# Driver.net
KiCad netlist of a schematic drawn in Altium Designer
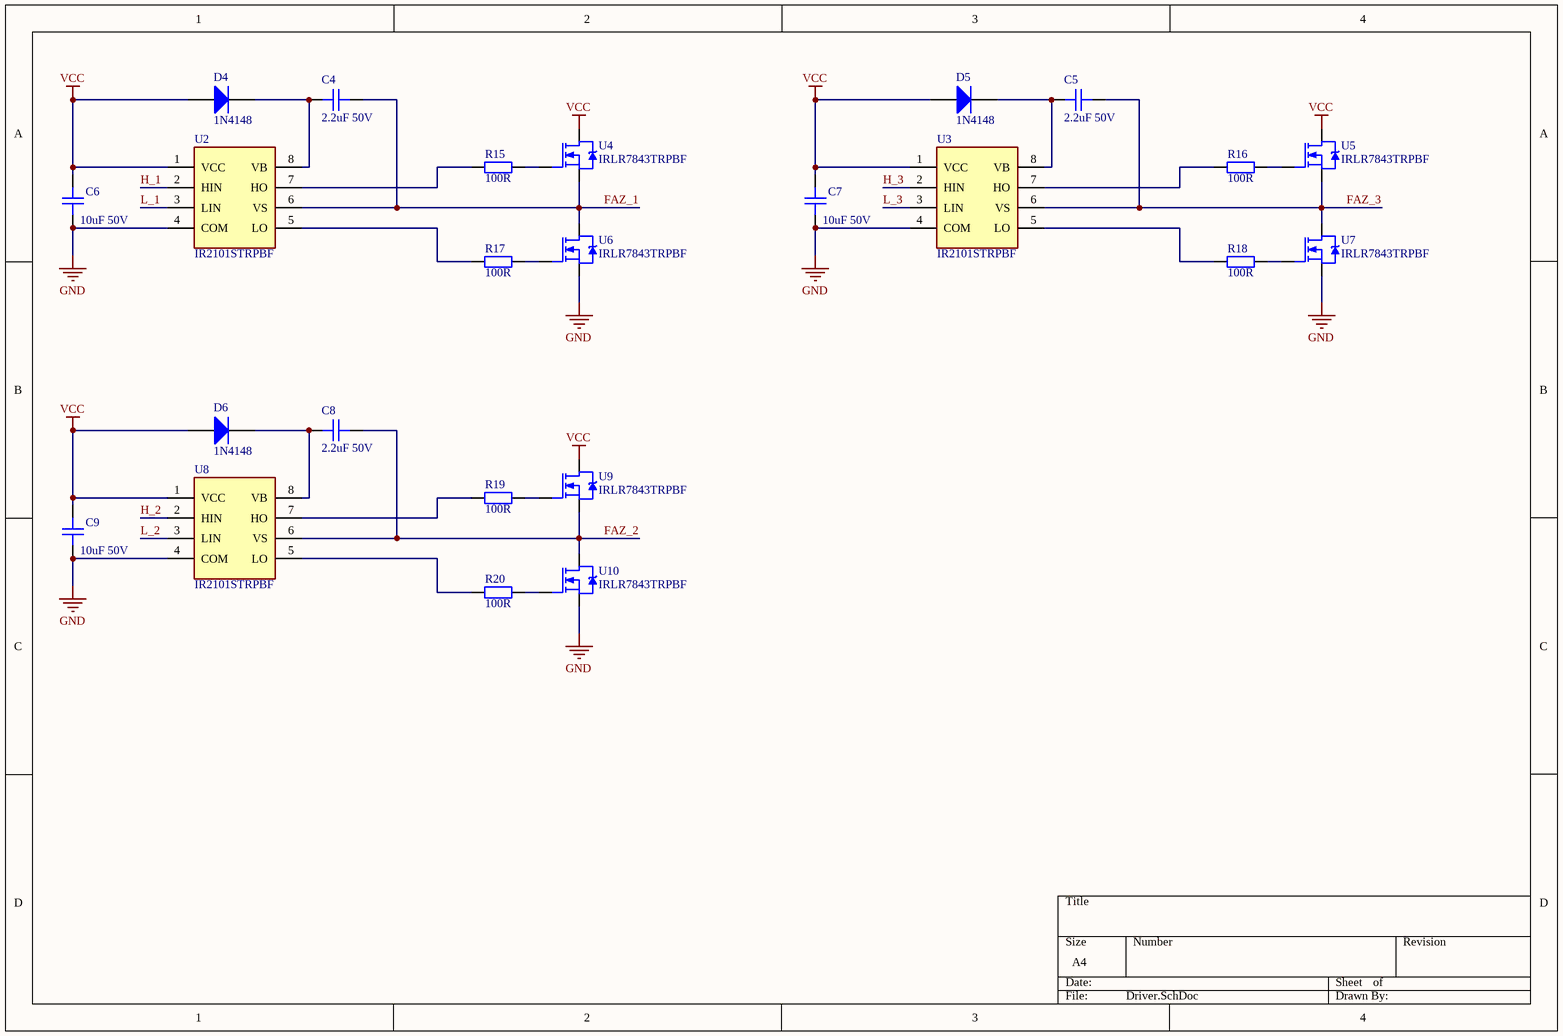
[diagram p0: Driver.SchDoc]

(export (version "E")
  (design (tool "Eeschema 10.0.6"))
  (components
    (comp (ref "C4")
      (value "CAP CER 2.2UF 50V X5R 1206")
      (footprint "CAP 1206/3216")
      (description "2.2µF ±10% 50V Ceramic Capacitor X5R 1206 (3216 Metric)")
      (fields (field (name "DEGER") "2.2uF 50V"))
      (libsource (lib "PROJE") (part "2.2uF 50V 1206"))
    )
    (comp (ref "C5")
      (value "CAP CER 2.2UF 50V X5R 1206")
      (footprint "CAP 1206/3216")
      (description "2.2µF ±10% 50V Ceramic Capacitor X5R 1206 (3216 Metric)")
      (fields (field (name "DEGER") "2.2uF 50V"))
      (libsource (lib "PROJE") (part "2.2uF 50V 1206"))
    )
    (comp (ref "C6")
      (value "CAP CER 10UF 50V X5R 1206")
      (footprint "CAP 1206/3216")
      (description "10µF ±10% 50V Ceramic Capacitor X5R 1206 (3216 Metric)")
      (fields (field (name "DEGER") "10uF 50V"))
      (libsource (lib "PROJE") (part "10uF 50V 1206"))
    )
    (comp (ref "C7")
      (value "CAP CER 10UF 50V X5R 1206")
      (footprint "CAP 1206/3216")
      (description "10µF ±10% 50V Ceramic Capacitor X5R 1206 (3216 Metric)")
      (fields (field (name "DEGER") "10uF 50V"))
      (libsource (lib "PROJE") (part "10uF 50V 1206"))
    )
    (comp (ref "C8")
      (value "CAP CER 2.2UF 50V X5R 1206")
      (footprint "CAP 1206/3216")
      (description "2.2µF ±10% 50V Ceramic Capacitor X5R 1206 (3216 Metric)")
      (fields (field (name "DEGER") "2.2uF 50V"))
      (libsource (lib "PROJE") (part "2.2uF 50V 1206"))
    )
    (comp (ref "C9")
      (value "CAP CER 10UF 50V X5R 1206")
      (footprint "CAP 1206/3216")
      (description "10µF ±10% 50V Ceramic Capacitor X5R 1206 (3216 Metric)")
      (fields (field (name "DEGER") "10uF 50V"))
      (libsource (lib "PROJE") (part "10uF 50V 1206"))
    )
    (comp (ref "D4")
      (value "1N4148 Diyot")
      (footprint "SOD-123")
      (description "DIODE GEN PURP 100V 150MA SOD123")
      (fields (field (name "DEGER") "1N4148"))
      (libsource (lib "PROJE") (part "1N4148"))
    )
    (comp (ref "D5")
      (value "1N4148 Diyot")
      (footprint "SOD-123")
      (description "DIODE GEN PURP 100V 150MA SOD123")
      (fields (field (name "DEGER") "1N4148"))
      (libsource (lib "PROJE") (part "1N4148"))
    )
    (comp (ref "D6")
      (value "1N4148 Diyot")
      (footprint "SOD-123")
      (description "DIODE GEN PURP 100V 150MA SOD123")
      (fields (field (name "DEGER") "1N4148"))
      (libsource (lib "PROJE") (part "1N4148"))
    )
    (comp (ref "R15")
      (value "RES SMD 100 OHM 1% 1/8W 0805")
      (footprint "RES_0805")
      (description "100 Ohms ±1% 0.125W, 1/8W Chip Resistor 0805 (2012 Metric) Moisture Resistant Thick Film")
      (fields (field (name "DEGER") "100R"))
      (libsource (lib "PROJE") (part "100R 0805"))
    )
    (comp (ref "R16")
      (value "RES SMD 100 OHM 1% 1/8W 0805")
      (footprint "RES_0805")
      (description "100 Ohms ±1% 0.125W, 1/8W Chip Resistor 0805 (2012 Metric) Moisture Resistant Thick Film")
      (fields (field (name "DEGER") "100R"))
      (libsource (lib "PROJE") (part "100R 0805"))
    )
    (comp (ref "R17")
      (value "RES SMD 100 OHM 1% 1/8W 0805")
      (footprint "RES_0805")
      (description "100 Ohms ±1% 0.125W, 1/8W Chip Resistor 0805 (2012 Metric) Moisture Resistant Thick Film")
      (fields (field (name "DEGER") "100R"))
      (libsource (lib "PROJE") (part "100R 0805"))
    )
    (comp (ref "R18")
      (value "RES SMD 100 OHM 1% 1/8W 0805")
      (footprint "RES_0805")
      (description "100 Ohms ±1% 0.125W, 1/8W Chip Resistor 0805 (2012 Metric) Moisture Resistant Thick Film")
      (fields (field (name "DEGER") "100R"))
      (libsource (lib "PROJE") (part "100R 0805"))
    )
    (comp (ref "R19")
      (value "RES SMD 100 OHM 1% 1/8W 0805")
      (footprint "RES_0805")
      (description "100 Ohms ±1% 0.125W, 1/8W Chip Resistor 0805 (2012 Metric) Moisture Resistant Thick Film")
      (fields (field (name "DEGER") "100R"))
      (libsource (lib "PROJE") (part "100R 0805"))
    )
    (comp (ref "R20")
      (value "RES SMD 100 OHM 1% 1/8W 0805")
      (footprint "RES_0805")
      (description "100 Ohms ±1% 0.125W, 1/8W Chip Resistor 0805 (2012 Metric) Moisture Resistant Thick Film")
      (fields (field (name "DEGER") "100R"))
      (libsource (lib "PROJE") (part "100R 0805"))
    )
    (comp (ref "U2")
      (value "IC GATE DRVR HALF-BRIDGE 8SOIC")
      (footprint "SOIC8")
      (description "Half-Bridge Gate Driver IC Non-Inverting 8-SOIC")
      (fields (field (name "DEGER") "IR2101STRPBF"))
      (libsource (lib "PROJE") (part "IR2101"))
    )
    (comp (ref "U3")
      (value "IC GATE DRVR HALF-BRIDGE 8SOIC")
      (footprint "SOIC8")
      (description "Half-Bridge Gate Driver IC Non-Inverting 8-SOIC")
      (fields (field (name "DEGER") "IR2101STRPBF"))
      (libsource (lib "PROJE") (part "IR2101"))
    )
    (comp (ref "U4")
      (value "MOSFET N-CH 30V 161A DPAK")
      (footprint "DPAK")
      (description "N-Channel 30V 161A (Tc) 140W (Tc) Surface Mount D-Pak")
      (fields (field (name "DEGER") "IRLR7843TRPBF"))
      (libsource (lib "PROJE") (part "IRLR7843"))
    )
    (comp (ref "U5")
      (value "MOSFET N-CH 30V 161A DPAK")
      (footprint "DPAK")
      (description "N-Channel 30V 161A (Tc) 140W (Tc) Surface Mount D-Pak")
      (fields (field (name "DEGER") "IRLR7843TRPBF"))
      (libsource (lib "PROJE") (part "IRLR7843"))
    )
    (comp (ref "U6")
      (value "MOSFET N-CH 30V 161A DPAK")
      (footprint "DPAK")
      (description "N-Channel 30V 161A (Tc) 140W (Tc) Surface Mount D-Pak")
      (fields (field (name "DEGER") "IRLR7843TRPBF"))
      (libsource (lib "PROJE") (part "IRLR7843"))
    )
    (comp (ref "U7")
      (value "MOSFET N-CH 30V 161A DPAK")
      (footprint "DPAK")
      (description "N-Channel 30V 161A (Tc) 140W (Tc) Surface Mount D-Pak")
      (fields (field (name "DEGER") "IRLR7843TRPBF"))
      (libsource (lib "PROJE") (part "IRLR7843"))
    )
    (comp (ref "U8")
      (value "IC GATE DRVR HALF-BRIDGE 8SOIC")
      (footprint "SOIC8")
      (description "Half-Bridge Gate Driver IC Non-Inverting 8-SOIC")
      (fields (field (name "DEGER") "IR2101STRPBF"))
      (libsource (lib "PROJE") (part "IR2101"))
    )
    (comp (ref "U9")
      (value "MOSFET N-CH 30V 161A DPAK")
      (footprint "DPAK")
      (description "N-Channel 30V 161A (Tc) 140W (Tc) Surface Mount D-Pak")
      (fields (field (name "DEGER") "IRLR7843TRPBF"))
      (libsource (lib "PROJE") (part "IRLR7843"))
    )
    (comp (ref "U10")
      (value "MOSFET N-CH 30V 161A DPAK")
      (footprint "DPAK")
      (description "N-Channel 30V 161A (Tc) 140W (Tc) Surface Mount D-Pak")
      (fields (field (name "DEGER") "IRLR7843TRPBF"))
      (libsource (lib "PROJE") (part "IRLR7843"))
    )
  )
  (nets
    (net (code "1") (name "/FAZ_1") (class "Default")
      (node (ref "C4") (pin "1") (pinfunction "1_1") (pintype "passive"))
      (node (ref "U2") (pin "6") (pinfunction "VS_6") (pintype "passive"))
      (node (ref "U4") (pin "3") (pinfunction "S_3") (pintype "passive"))
      (node (ref "U6") (pin "4") (pinfunction "D_4") (pintype "passive"))
    )
    (net (code "2") (name "/FAZ_2") (class "Default")
      (node (ref "C8") (pin "1") (pinfunction "1_1") (pintype "passive"))
      (node (ref "U10") (pin "4") (pinfunction "D_4") (pintype "passive"))
      (node (ref "U8") (pin "6") (pinfunction "VS_6") (pintype "passive"))
      (node (ref "U9") (pin "3") (pinfunction "S_3") (pintype "passive"))
    )
    (net (code "3") (name "/FAZ_3") (class "Default")
      (node (ref "C5") (pin "1") (pinfunction "1_1") (pintype "passive"))
      (node (ref "U3") (pin "6") (pinfunction "VS_6") (pintype "passive"))
      (node (ref "U5") (pin "3") (pinfunction "S_3") (pintype "passive"))
      (node (ref "U7") (pin "4") (pinfunction "D_4") (pintype "passive"))
    )
    (net (code "4") (name "/H_1") (class "Default")
      (node (ref "U2") (pin "2") (pinfunction "HIN_2") (pintype "passive"))
    )
    (net (code "5") (name "/H_2") (class "Default")
      (node (ref "U8") (pin "2") (pinfunction "HIN_2") (pintype "passive"))
    )
    (net (code "6") (name "/H_3") (class "Default")
      (node (ref "U3") (pin "2") (pinfunction "HIN_2") (pintype "passive"))
    )
    (net (code "7") (name "/L_1") (class "Default")
      (node (ref "U2") (pin "3") (pinfunction "LIN_3") (pintype "passive"))
    )
    (net (code "8") (name "/L_2") (class "Default")
      (node (ref "U8") (pin "3") (pinfunction "LIN_3") (pintype "passive"))
    )
    (net (code "9") (name "/L_3") (class "Default")
      (node (ref "U3") (pin "3") (pinfunction "LIN_3") (pintype "passive"))
    )
    (net (code "10") (name "GND") (class "Default")
      (node (ref "C6") (pin "1") (pinfunction "1_1") (pintype "passive"))
      (node (ref "C7") (pin "1") (pinfunction "1_1") (pintype "passive"))
      (node (ref "C9") (pin "1") (pinfunction "1_1") (pintype "passive"))
      (node (ref "U10") (pin "3") (pinfunction "S_3") (pintype "passive"))
      (node (ref "U2") (pin "4") (pinfunction "COM_4") (pintype "passive"))
      (node (ref "U3") (pin "4") (pinfunction "COM_4") (pintype "passive"))
      (node (ref "U6") (pin "3") (pinfunction "S_3") (pintype "passive"))
      (node (ref "U7") (pin "3") (pinfunction "S_3") (pintype "passive"))
      (node (ref "U8") (pin "4") (pinfunction "COM_4") (pintype "passive"))
    )
    (net (code "11") (name "Net-(D4-K)") (class "Default")
      (node (ref "C4") (pin "2") (pinfunction "2_2") (pintype "passive"))
      (node (ref "D4") (pin "2") (pinfunction "K_2") (pintype "passive"))
      (node (ref "U2") (pin "8") (pinfunction "VB_8") (pintype "passive"))
    )
    (net (code "12") (name "Net-(D5-K)") (class "Default")
      (node (ref "C5") (pin "2") (pinfunction "2_2") (pintype "passive"))
      (node (ref "D5") (pin "2") (pinfunction "K_2") (pintype "passive"))
      (node (ref "U3") (pin "8") (pinfunction "VB_8") (pintype "passive"))
    )
    (net (code "13") (name "Net-(D6-K)") (class "Default")
      (node (ref "C8") (pin "2") (pinfunction "2_2") (pintype "passive"))
      (node (ref "D6") (pin "2") (pinfunction "K_2") (pintype "passive"))
      (node (ref "U8") (pin "8") (pinfunction "VB_8") (pintype "passive"))
    )
    (net (code "14") (name "Net-(U2-HO)") (class "Default")
      (node (ref "R15") (pin "1") (pinfunction "1_1") (pintype "passive"))
      (node (ref "U2") (pin "7") (pinfunction "HO_7") (pintype "passive"))
    )
    (net (code "15") (name "Net-(U2-LO)") (class "Default")
      (node (ref "R17") (pin "1") (pinfunction "1_1") (pintype "passive"))
      (node (ref "U2") (pin "5") (pinfunction "LO_5") (pintype "passive"))
    )
    (net (code "16") (name "Net-(U3-HO)") (class "Default")
      (node (ref "R16") (pin "1") (pinfunction "1_1") (pintype "passive"))
      (node (ref "U3") (pin "7") (pinfunction "HO_7") (pintype "passive"))
    )
    (net (code "17") (name "Net-(U3-LO)") (class "Default")
      (node (ref "R18") (pin "1") (pinfunction "1_1") (pintype "passive"))
      (node (ref "U3") (pin "5") (pinfunction "LO_5") (pintype "passive"))
    )
    (net (code "18") (name "Net-(U4-G)") (class "Default")
      (node (ref "R15") (pin "2") (pinfunction "2_2") (pintype "passive"))
      (node (ref "U4") (pin "1") (pinfunction "G_1") (pintype "passive"))
    )
    (net (code "19") (name "Net-(U5-G)") (class "Default")
      (node (ref "R16") (pin "2") (pinfunction "2_2") (pintype "passive"))
      (node (ref "U5") (pin "1") (pinfunction "G_1") (pintype "passive"))
    )
    (net (code "20") (name "Net-(U6-G)") (class "Default")
      (node (ref "R17") (pin "2") (pinfunction "2_2") (pintype "passive"))
      (node (ref "U6") (pin "1") (pinfunction "G_1") (pintype "passive"))
    )
    (net (code "21") (name "Net-(U7-G)") (class "Default")
      (node (ref "R18") (pin "2") (pinfunction "2_2") (pintype "passive"))
      (node (ref "U7") (pin "1") (pinfunction "G_1") (pintype "passive"))
    )
    (net (code "22") (name "Net-(U8-HO)") (class "Default")
      (node (ref "R19") (pin "1") (pinfunction "1_1") (pintype "passive"))
      (node (ref "U8") (pin "7") (pinfunction "HO_7") (pintype "passive"))
    )
    (net (code "23") (name "Net-(U8-LO)") (class "Default")
      (node (ref "R20") (pin "1") (pinfunction "1_1") (pintype "passive"))
      (node (ref "U8") (pin "5") (pinfunction "LO_5") (pintype "passive"))
    )
    (net (code "24") (name "Net-(U9-G)") (class "Default")
      (node (ref "R19") (pin "2") (pinfunction "2_2") (pintype "passive"))
      (node (ref "U9") (pin "1") (pinfunction "G_1") (pintype "passive"))
    )
    (net (code "25") (name "Net-(U10-G)") (class "Default")
      (node (ref "R20") (pin "2") (pinfunction "2_2") (pintype "passive"))
      (node (ref "U10") (pin "1") (pinfunction "G_1") (pintype "passive"))
    )
    (net (code "26") (name "VCC") (class "Default")
      (node (ref "C6") (pin "2") (pinfunction "2_2") (pintype "passive"))
      (node (ref "C7") (pin "2") (pinfunction "2_2") (pintype "passive"))
      (node (ref "C9") (pin "2") (pinfunction "2_2") (pintype "passive"))
      (node (ref "D4") (pin "1") (pinfunction "A_1") (pintype "passive"))
      (node (ref "D5") (pin "1") (pinfunction "A_1") (pintype "passive"))
      (node (ref "D6") (pin "1") (pinfunction "A_1") (pintype "passive"))
      (node (ref "U2") (pin "1") (pinfunction "VCC_1") (pintype "passive"))
      (node (ref "U3") (pin "1") (pinfunction "VCC_1") (pintype "passive"))
      (node (ref "U4") (pin "4") (pinfunction "D_4") (pintype "passive"))
      (node (ref "U5") (pin "4") (pinfunction "D_4") (pintype "passive"))
      (node (ref "U8") (pin "1") (pinfunction "VCC_1") (pintype "passive"))
      (node (ref "U9") (pin "4") (pinfunction "D_4") (pintype "passive"))
    )
  )
)
